# ASCII_04_LMS7002M_Misc.net
KiCad netlist of a schematic drawn in Altium Designer
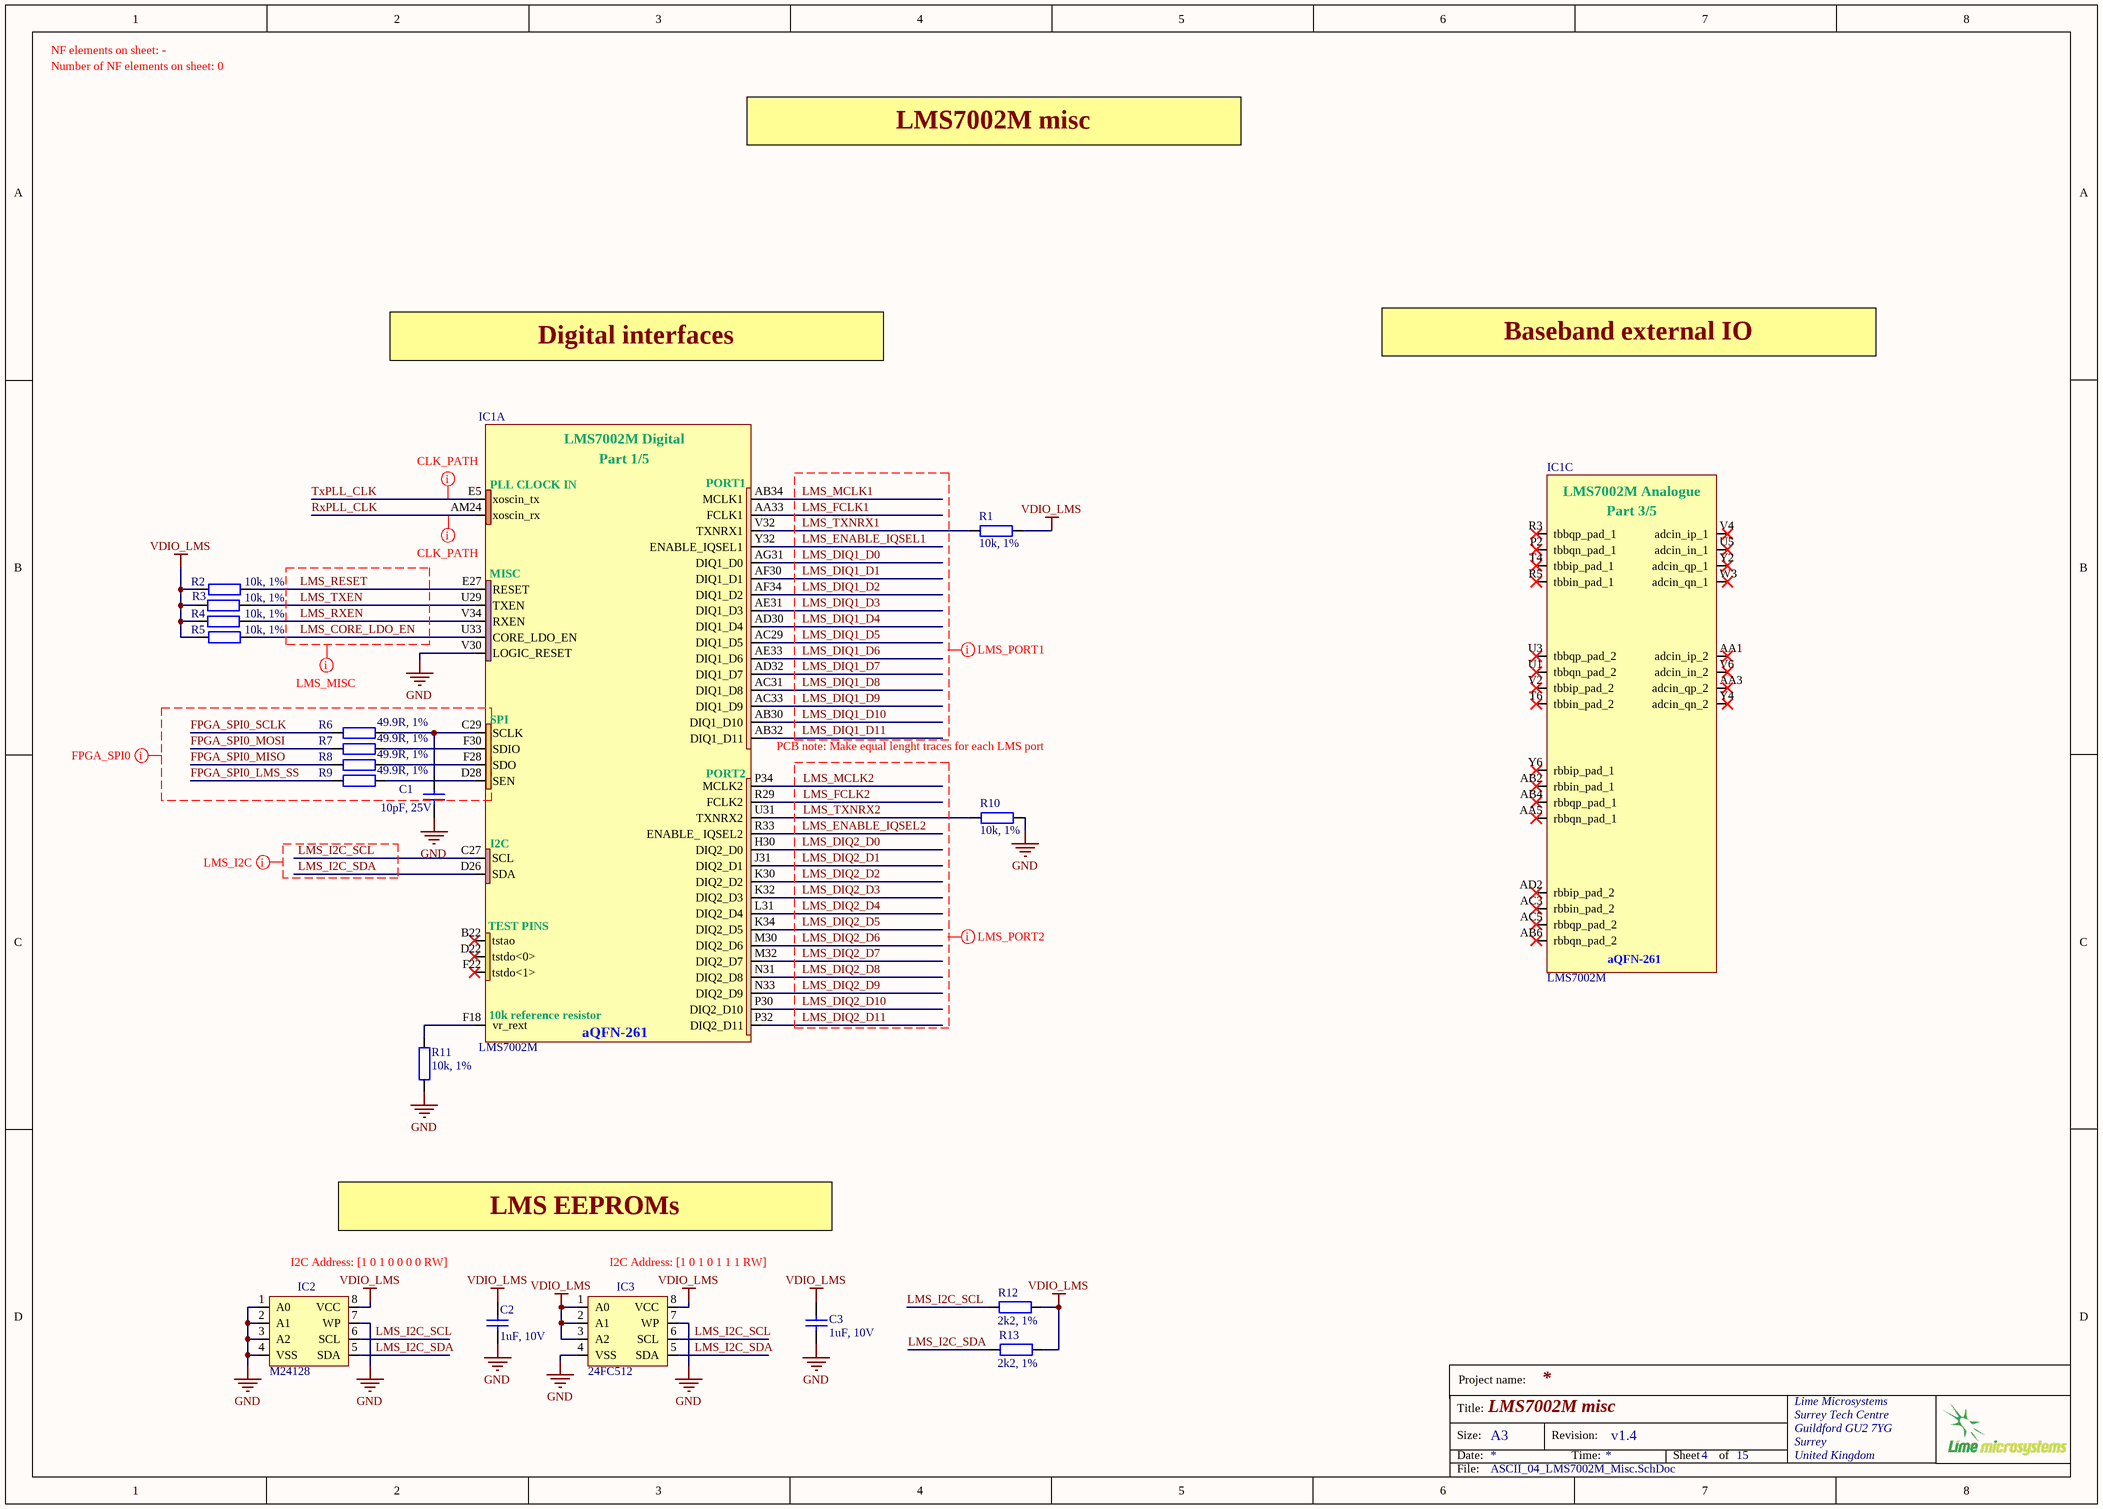
[diagram p0: ASCII_04_LMS7002M_Misc.SchDoc]

(export (version "E")
  (design (tool "Eeschema 10.0.6"))
  (components
    (comp (ref "C1")
      (value "10pF, 25V")
      (footprint "CAP0402")
      (fields (field (name "MANUFACTURER") "AVX"))
      (libsource (lib "LimeMicroAltiumLib_schLib") (part "Cap_0402"))
    )
    (comp (ref "C2")
      (value "1uF, 10V")
      (footprint "CAP0402")
      (fields (field (name "MANUFACTURER") "TDK"))
      (libsource (lib "LimeMicroAltiumLib_schLib") (part "Cap_0402"))
    )
    (comp (ref "C3")
      (value "1uF, 10V")
      (footprint "CAP0402")
      (fields (field (name "MANUFACTURER") "TDK"))
      (libsource (lib "LimeMicroAltiumLib_schLib") (part "Cap_0402"))
    )
    (comp (ref "IC1")
      (value "LMS7002M")
      (footprint "LMS7002M_v3")
      (fields (field (name "MANUFACTURER") "Lime Microsystems"))
      (libsource (lib "LimeMicroAltiumLib_schLib") (part "LMS7002M"))
    )
    (comp (ref "IC2")
      (value "M24128")
      (footprint "24FC512")
      (fields (field (name "MANUFACTURER") "STMicroelectronics"))
      (libsource (lib "LimeMicroAltiumLib_schLib") (part "24FC64F"))
    )
    (comp (ref "IC3")
      (value "24FC512")
      (footprint "24FC512")
      (fields (field (name "MANUFACTURER") "Microchip Technology"))
      (libsource (lib "LimeMicroAltiumLib_schLib") (part "24FC512"))
    )
    (comp (ref "R1")
      (value "10k, 1%")
      (footprint "RES0402")
      (fields (field (name "MANUFACTURER") "Yageo") (field (name "TOLERANCE") "±1%"))
      (libsource (lib "LimeMicroAltiumLib_schLib") (part "Res_0402"))
    )
    (comp (ref "R2")
      (value "10k, 1%")
      (footprint "RES0402")
      (fields (field (name "MANUFACTURER") "Yageo") (field (name "TOLERANCE") "±1%"))
      (libsource (lib "LimeMicroAltiumLib_schLib") (part "Res_0402"))
    )
    (comp (ref "R3")
      (value "10k, 1%")
      (footprint "RES0402")
      (fields (field (name "MANUFACTURER") "Yageo") (field (name "TOLERANCE") "±1%"))
      (libsource (lib "LimeMicroAltiumLib_schLib") (part "Res_0402"))
    )
    (comp (ref "R4")
      (value "10k, 1%")
      (footprint "RES0402")
      (fields (field (name "MANUFACTURER") "Yageo") (field (name "TOLERANCE") "±1%"))
      (libsource (lib "LimeMicroAltiumLib_schLib") (part "Res_0402"))
    )
    (comp (ref "R5")
      (value "10k, 1%")
      (footprint "RES0402")
      (fields (field (name "MANUFACTURER") "Yageo") (field (name "TOLERANCE") "±1%"))
      (libsource (lib "LimeMicroAltiumLib_schLib") (part "Res_0402"))
    )
    (comp (ref "R6")
      (value "49.9R, 1%")
      (footprint "RES0402")
      (fields
        (field (name "TOLERANCE") "±1%")
        (field (name "MANUFACTURER") "Samsung Electro-Mechanics America, Inc.")
        (field (name "MANUFACTURER PART NUMBER") "RC1005F49R9CS")
      )
      (libsource (lib "LimeMicroAltiumLib_schLib") (part "Res_0402"))
    )
    (comp (ref "R7")
      (value "49.9R, 1%")
      (footprint "RES0402")
      (fields
        (field (name "TOLERANCE") "±1%")
        (field (name "MANUFACTURER") "Samsung Electro-Mechanics America, Inc.")
        (field (name "MANUFACTURER PART NUMBER") "RC1005F49R9CS")
      )
      (libsource (lib "LimeMicroAltiumLib_schLib") (part "Res_0402"))
    )
    (comp (ref "R8")
      (value "49.9R, 1%")
      (footprint "RES0402")
      (fields
        (field (name "TOLERANCE") "±1%")
        (field (name "MANUFACTURER") "Samsung Electro-Mechanics America, Inc.")
        (field (name "MANUFACTURER PART NUMBER") "RC1005F49R9CS")
      )
      (libsource (lib "LimeMicroAltiumLib_schLib") (part "Res_0402"))
    )
    (comp (ref "R9")
      (value "49.9R, 1%")
      (footprint "RES0402")
      (fields
        (field (name "TOLERANCE") "±1%")
        (field (name "MANUFACTURER") "Samsung Electro-Mechanics America, Inc.")
        (field (name "MANUFACTURER PART NUMBER") "RC1005F49R9CS")
      )
      (libsource (lib "LimeMicroAltiumLib_schLib") (part "Res_0402"))
    )
    (comp (ref "R10")
      (value "10k, 1%")
      (footprint "RES0402")
      (fields (field (name "MANUFACTURER") "Yageo") (field (name "TOLERANCE") "±1%"))
      (libsource (lib "LimeMicroAltiumLib_schLib") (part "Res_0402"))
    )
    (comp (ref "R11")
      (value "10k, 1%")
      (footprint "RES0402")
      (fields (field (name "MANUFACTURER") "Yageo") (field (name "TOLERANCE") "±1%"))
      (libsource (lib "LimeMicroAltiumLib_schLib") (part "Res_0402"))
    )
    (comp (ref "R12")
      (value "2k2, 1%")
      (footprint "RES0402")
      (fields (field (name "MANUFACTURER") "Stackpole Electronics Inc") (field (name "TOLERANCE") "±1%"))
      (libsource (lib "LimeMicroAltiumLib_schLib") (part "Res_0402"))
    )
    (comp (ref "R13")
      (value "2k2, 1%")
      (footprint "RES0402")
      (fields (field (name "MANUFACTURER") "Stackpole Electronics Inc") (field (name "TOLERANCE") "±1%"))
      (libsource (lib "LimeMicroAltiumLib_schLib") (part "Res_0402"))
    )
  )
  (nets
    (net (code "1") (name "/FPGA_SPI0_LMS_SS") (class "Default")
      (node (ref "R9") (pin "2") (pinfunction "2_2") (pintype "passive"))
    )
    (net (code "2") (name "/FPGA_SPI0_MISO") (class "Default")
      (node (ref "R8") (pin "2") (pinfunction "2_2") (pintype "passive"))
    )
    (net (code "3") (name "/FPGA_SPI0_MOSI") (class "Default")
      (node (ref "R7") (pin "2") (pinfunction "2_2") (pintype "passive"))
    )
    (net (code "4") (name "/FPGA_SPI0_SCLK") (class "Default")
      (node (ref "R6") (pin "2") (pinfunction "2_2") (pintype "passive"))
    )
    (net (code "5") (name "/LMS_CORE_LDO_EN") (class "Default")
      (node (ref "IC1") (pin "U33") (pinfunction "CORE_LDO_EN_U33") (pintype "passive"))
      (node (ref "R5") (pin "1") (pinfunction "1_1") (pintype "passive"))
    )
    (net (code "6") (name "/LMS_DIQ1_D0") (class "Default")
      (node (ref "IC1") (pin "AG31") (pinfunction "DIQ1_D0_AG31") (pintype "passive"))
    )
    (net (code "7") (name "/LMS_DIQ1_D1") (class "Default")
      (node (ref "IC1") (pin "AF30") (pinfunction "DIQ1_D1_AF30") (pintype "passive"))
    )
    (net (code "8") (name "/LMS_DIQ1_D2") (class "Default")
      (node (ref "IC1") (pin "AF34") (pinfunction "DIQ1_D2_AF34") (pintype "passive"))
    )
    (net (code "9") (name "/LMS_DIQ1_D3") (class "Default")
      (node (ref "IC1") (pin "AE31") (pinfunction "DIQ1_D3_AE31") (pintype "passive"))
    )
    (net (code "10") (name "/LMS_DIQ1_D4") (class "Default")
      (node (ref "IC1") (pin "AD30") (pinfunction "DIQ1_D4_AD30") (pintype "passive"))
    )
    (net (code "11") (name "/LMS_DIQ1_D5") (class "Default")
      (node (ref "IC1") (pin "AC29") (pinfunction "DIQ1_D5_AC29") (pintype "passive"))
    )
    (net (code "12") (name "/LMS_DIQ1_D6") (class "Default")
      (node (ref "IC1") (pin "AE33") (pinfunction "DIQ1_D6_AE33") (pintype "passive"))
    )
    (net (code "13") (name "/LMS_DIQ1_D7") (class "Default")
      (node (ref "IC1") (pin "AD32") (pinfunction "DIQ1_D7_AD32") (pintype "passive"))
    )
    (net (code "14") (name "/LMS_DIQ1_D8") (class "Default")
      (node (ref "IC1") (pin "AC31") (pinfunction "DIQ1_D8_AC31") (pintype "passive"))
    )
    (net (code "15") (name "/LMS_DIQ1_D9") (class "Default")
      (node (ref "IC1") (pin "AC33") (pinfunction "DIQ1_D9_AC33") (pintype "passive"))
    )
    (net (code "16") (name "/LMS_DIQ1_D10") (class "Default")
      (node (ref "IC1") (pin "AB30") (pinfunction "DIQ1_D10_AB30") (pintype "passive"))
    )
    (net (code "17") (name "/LMS_DIQ1_D11") (class "Default")
      (node (ref "IC1") (pin "AB32") (pinfunction "DIQ1_D11_AB32") (pintype "passive"))
    )
    (net (code "18") (name "/LMS_DIQ2_D0") (class "Default")
      (node (ref "IC1") (pin "H30") (pinfunction "DIQ2_D0_H30") (pintype "passive"))
    )
    (net (code "19") (name "/LMS_DIQ2_D1") (class "Default")
      (node (ref "IC1") (pin "J31") (pinfunction "DIQ2_D1_J31") (pintype "passive"))
    )
    (net (code "20") (name "/LMS_DIQ2_D2") (class "Default")
      (node (ref "IC1") (pin "K30") (pinfunction "DIQ2_D2_K30") (pintype "passive"))
    )
    (net (code "21") (name "/LMS_DIQ2_D3") (class "Default")
      (node (ref "IC1") (pin "K32") (pinfunction "DIQ2_D3_K32") (pintype "passive"))
    )
    (net (code "22") (name "/LMS_DIQ2_D4") (class "Default")
      (node (ref "IC1") (pin "L31") (pinfunction "DIQ2_D4_L31") (pintype "passive"))
    )
    (net (code "23") (name "/LMS_DIQ2_D5") (class "Default")
      (node (ref "IC1") (pin "K34") (pinfunction "DIQ2_D5_K34") (pintype "passive"))
    )
    (net (code "24") (name "/LMS_DIQ2_D6") (class "Default")
      (node (ref "IC1") (pin "M30") (pinfunction "DIQ2_D6_M30") (pintype "passive"))
    )
    (net (code "25") (name "/LMS_DIQ2_D7") (class "Default")
      (node (ref "IC1") (pin "M32") (pinfunction "DIQ2_D7_M32") (pintype "passive"))
    )
    (net (code "26") (name "/LMS_DIQ2_D8") (class "Default")
      (node (ref "IC1") (pin "N31") (pinfunction "DIQ2_D8_N31") (pintype "passive"))
    )
    (net (code "27") (name "/LMS_DIQ2_D9") (class "Default")
      (node (ref "IC1") (pin "N33") (pinfunction "DIQ2_D9_N33") (pintype "passive"))
    )
    (net (code "28") (name "/LMS_DIQ2_D10") (class "Default")
      (node (ref "IC1") (pin "P30") (pinfunction "DIQ2_D10_P30") (pintype "passive"))
    )
    (net (code "29") (name "/LMS_DIQ2_D11") (class "Default")
      (node (ref "IC1") (pin "P32") (pinfunction "DIQ2_D11_P32") (pintype "passive"))
    )
    (net (code "30") (name "/LMS_ENABLE_IQSEL1") (class "Default")
      (node (ref "IC1") (pin "Y32") (pinfunction "ENABLE_IQSEL1_Y32") (pintype "passive"))
    )
    (net (code "31") (name "/LMS_ENABLE_IQSEL2") (class "Default")
      (node (ref "IC1") (pin "R33") (pinfunction "ENABLE__IQSEL2_R33") (pintype "passive"))
    )
    (net (code "32") (name "/LMS_FCLK1") (class "Default")
      (node (ref "IC1") (pin "AA33") (pinfunction "FCLK1_AA33") (pintype "passive"))
    )
    (net (code "33") (name "/LMS_FCLK2") (class "Default")
      (node (ref "IC1") (pin "R29") (pinfunction "FCLK2_R29") (pintype "passive"))
    )
    (net (code "34") (name "/LMS_I2C_SCL") (class "Default")
      (node (ref "IC1") (pin "C27") (pinfunction "SCL_C27") (pintype "passive"))
      (node (ref "IC2") (pin "6") (pinfunction "SCL_6") (pintype "passive"))
      (node (ref "IC3") (pin "6") (pinfunction "SCL_6") (pintype "passive"))
      (node (ref "R12") (pin "2") (pinfunction "2_2") (pintype "passive"))
    )
    (net (code "35") (name "/LMS_I2C_SDA") (class "Default")
      (node (ref "IC1") (pin "D26") (pinfunction "SDA_D26") (pintype "passive"))
      (node (ref "IC2") (pin "5") (pinfunction "SDA_5") (pintype "passive"))
      (node (ref "IC3") (pin "5") (pinfunction "SDA_5") (pintype "passive"))
      (node (ref "R13") (pin "2") (pinfunction "2_2") (pintype "passive"))
    )
    (net (code "36") (name "/LMS_MCLK1") (class "Default")
      (node (ref "IC1") (pin "AB34") (pinfunction "MCLK1_AB34") (pintype "passive"))
    )
    (net (code "37") (name "/LMS_MCLK2") (class "Default")
      (node (ref "IC1") (pin "P34") (pinfunction "MCLK2_P34") (pintype "passive"))
    )
    (net (code "38") (name "/LMS_RESET") (class "Default")
      (node (ref "IC1") (pin "E27") (pinfunction "RESET_E27") (pintype "passive"))
      (node (ref "R2") (pin "1") (pinfunction "1_1") (pintype "passive"))
    )
    (net (code "39") (name "/LMS_RXEN") (class "Default")
      (node (ref "IC1") (pin "V34") (pinfunction "RXEN_V34") (pintype "passive"))
      (node (ref "R4") (pin "2") (pinfunction "2_2") (pintype "passive"))
    )
    (net (code "40") (name "/LMS_TXEN") (class "Default")
      (node (ref "IC1") (pin "U29") (pinfunction "TXEN_U29") (pintype "passive"))
      (node (ref "R3") (pin "2") (pinfunction "2_2") (pintype "passive"))
    )
    (net (code "41") (name "/LMS_TXNRX1") (class "Default")
      (node (ref "IC1") (pin "V32") (pinfunction "TXNRX1_V32") (pintype "passive"))
      (node (ref "R1") (pin "1") (pinfunction "1_1") (pintype "passive"))
    )
    (net (code "42") (name "/LMS_TXNRX2") (class "Default")
      (node (ref "IC1") (pin "U31") (pinfunction "TXNRX2_U31") (pintype "passive"))
      (node (ref "R10") (pin "2") (pinfunction "2_2") (pintype "passive"))
    )
    (net (code "43") (name "/RxPLL_CLK") (class "Default")
      (node (ref "IC1") (pin "AM24") (pinfunction "xoscin_rx_AM24") (pintype "passive"))
    )
    (net (code "44") (name "/TxPLL_CLK") (class "Default")
      (node (ref "IC1") (pin "E5") (pinfunction "xoscin_tx_E5") (pintype "passive"))
    )
    (net (code "45") (name "GND") (class "Default")
      (node (ref "C1") (pin "2") (pinfunction "2_2") (pintype "passive"))
      (node (ref "C2") (pin "2") (pinfunction "2_2") (pintype "passive"))
      (node (ref "C3") (pin "1") (pinfunction "1_1") (pintype "passive"))
      (node (ref "IC1") (pin "V30") (pinfunction "LOGIC_RESET_V30") (pintype "passive"))
      (node (ref "IC2") (pin "1") (pinfunction "A0_1") (pintype "passive"))
      (node (ref "IC2") (pin "2") (pinfunction "A1_2") (pintype "passive"))
      (node (ref "IC2") (pin "3") (pinfunction "A2_3") (pintype "passive"))
      (node (ref "IC2") (pin "4") (pinfunction "VSS_4") (pintype "passive"))
      (node (ref "IC2") (pin "7") (pinfunction "WP_7") (pintype "passive"))
      (node (ref "IC3") (pin "4") (pinfunction "VSS_4") (pintype "passive"))
      (node (ref "IC3") (pin "7") (pinfunction "WP_7") (pintype "passive"))
      (node (ref "R10") (pin "1") (pinfunction "1_1") (pintype "passive"))
      (node (ref "R11") (pin "2") (pinfunction "2_2") (pintype "passive"))
    )
    (net (code "46") (name "Net-(IC1A-SCLK)") (class "Default")
      (node (ref "C1") (pin "1") (pinfunction "1_1") (pintype "passive"))
      (node (ref "IC1") (pin "C29") (pinfunction "SCLK_C29") (pintype "passive"))
      (node (ref "R6") (pin "1") (pinfunction "1_1") (pintype "passive"))
    )
    (net (code "47") (name "Net-(IC1A-SDIO)") (class "Default")
      (node (ref "IC1") (pin "F30") (pinfunction "SDIO_F30") (pintype "passive"))
      (node (ref "R7") (pin "1") (pinfunction "1_1") (pintype "passive"))
    )
    (net (code "48") (name "Net-(IC1A-SDO)") (class "Default")
      (node (ref "IC1") (pin "F28") (pinfunction "SDO_F28") (pintype "passive"))
      (node (ref "R8") (pin "1") (pinfunction "1_1") (pintype "passive"))
    )
    (net (code "49") (name "Net-(IC1A-SEN)") (class "Default")
      (node (ref "IC1") (pin "D28") (pinfunction "SEN_D28") (pintype "passive"))
      (node (ref "R9") (pin "1") (pinfunction "1_1") (pintype "passive"))
    )
    (net (code "50") (name "Net-(IC1A-vr_rext)") (class "Default")
      (node (ref "IC1") (pin "F18") (pinfunction "vr_rext_F18") (pintype "passive"))
      (node (ref "R11") (pin "1") (pinfunction "1_1") (pintype "passive"))
    )
    (net (code "51") (name "VDIO_LMS") (class "Default")
      (node (ref "C2") (pin "1") (pinfunction "1_1") (pintype "passive"))
      (node (ref "C3") (pin "2") (pinfunction "2_2") (pintype "passive"))
      (node (ref "IC2") (pin "8") (pinfunction "VCC_8") (pintype "passive"))
      (node (ref "IC3") (pin "1") (pinfunction "A0_1") (pintype "passive"))
      (node (ref "IC3") (pin "2") (pinfunction "A1_2") (pintype "passive"))
      (node (ref "IC3") (pin "3") (pinfunction "A2_3") (pintype "passive"))
      (node (ref "IC3") (pin "8") (pinfunction "VCC_8") (pintype "passive"))
      (node (ref "R1") (pin "2") (pinfunction "2_2") (pintype "passive"))
      (node (ref "R12") (pin "1") (pinfunction "1_1") (pintype "passive"))
      (node (ref "R13") (pin "1") (pinfunction "1_1") (pintype "passive"))
      (node (ref "R2") (pin "2") (pinfunction "2_2") (pintype "passive"))
      (node (ref "R3") (pin "1") (pinfunction "1_1") (pintype "passive"))
      (node (ref "R4") (pin "1") (pinfunction "1_1") (pintype "passive"))
      (node (ref "R5") (pin "2") (pinfunction "2_2") (pintype "passive"))
    )
    (net (code "52") (name "unconnected-(IC1A-tstao-PadB22)") (class "Default")
      (node (ref "IC1") (pin "B22") (pinfunction "tstao_B22") (pintype "passive+no_connect"))
    )
    (net (code "53") (name "unconnected-(IC1A-tstdo<0>-PadD22)") (class "Default")
      (node (ref "IC1") (pin "D22") (pinfunction "tstdo<0>_D22") (pintype "passive+no_connect"))
    )
    (net (code "54") (name "unconnected-(IC1A-tstdo<1>-PadF22)") (class "Default")
      (node (ref "IC1") (pin "F22") (pinfunction "tstdo<1>_F22") (pintype "passive+no_connect"))
    )
    (net (code "55") (name "unconnected-(IC1C-adcin_in_1-PadU5)") (class "Default")
      (node (ref "IC1") (pin "U5") (pinfunction "adcin_in_1_U5") (pintype "passive+no_connect"))
    )
    (net (code "56") (name "unconnected-(IC1C-adcin_in_2-PadV6)") (class "Default")
      (node (ref "IC1") (pin "V6") (pinfunction "adcin_in_2_V6") (pintype "passive+no_connect"))
    )
    (net (code "57") (name "unconnected-(IC1C-adcin_ip_1-PadV4)") (class "Default")
      (node (ref "IC1") (pin "V4") (pinfunction "adcin_ip_1_V4") (pintype "passive+no_connect"))
    )
    (net (code "58") (name "unconnected-(IC1C-adcin_ip_2-PadAA1)") (class "Default")
      (node (ref "IC1") (pin "AA1") (pinfunction "adcin_ip_2_AA1") (pintype "passive+no_connect"))
    )
    (net (code "59") (name "unconnected-(IC1C-adcin_qn_1-PadW3)") (class "Default")
      (node (ref "IC1") (pin "W3") (pinfunction "adcin_qn_1_W3") (pintype "passive+no_connect"))
    )
    (net (code "60") (name "unconnected-(IC1C-adcin_qn_2-PadY4)") (class "Default")
      (node (ref "IC1") (pin "Y4") (pinfunction "adcin_qn_2_Y4") (pintype "passive+no_connect"))
    )
    (net (code "61") (name "unconnected-(IC1C-adcin_qp_1-PadY2)") (class "Default")
      (node (ref "IC1") (pin "Y2") (pinfunction "adcin_qp_1_Y2") (pintype "passive+no_connect"))
    )
    (net (code "62") (name "unconnected-(IC1C-adcin_qp_2-PadAA3)") (class "Default")
      (node (ref "IC1") (pin "AA3") (pinfunction "adcin_qp_2_AA3") (pintype "passive+no_connect"))
    )
    (net (code "63") (name "unconnected-(IC1C-rbbin_pad_1-PadAB2)") (class "Default")
      (node (ref "IC1") (pin "AB2") (pinfunction "rbbin_pad_1_AB2") (pintype "passive+no_connect"))
    )
    (net (code "64") (name "unconnected-(IC1C-rbbin_pad_2-PadAC3)") (class "Default")
      (node (ref "IC1") (pin "AC3") (pinfunction "rbbin_pad_2_AC3") (pintype "passive+no_connect"))
    )
    (net (code "65") (name "unconnected-(IC1C-rbbip_pad_1-PadY6)") (class "Default")
      (node (ref "IC1") (pin "Y6") (pinfunction "rbbip_pad_1_Y6") (pintype "passive+no_connect"))
    )
    (net (code "66") (name "unconnected-(IC1C-rbbip_pad_2-PadAD2)") (class "Default")
      (node (ref "IC1") (pin "AD2") (pinfunction "rbbip_pad_2_AD2") (pintype "passive+no_connect"))
    )
    (net (code "67") (name "unconnected-(IC1C-rbbqn_pad_1-PadAA5)") (class "Default")
      (node (ref "IC1") (pin "AA5") (pinfunction "rbbqn_pad_1_AA5") (pintype "passive+no_connect"))
    )
    (net (code "68") (name "unconnected-(IC1C-rbbqn_pad_2-PadAB6)") (class "Default")
      (node (ref "IC1") (pin "AB6") (pinfunction "rbbqn_pad_2_AB6") (pintype "passive+no_connect"))
    )
    (net (code "69") (name "unconnected-(IC1C-rbbqp_pad_1-PadAB4)") (class "Default")
      (node (ref "IC1") (pin "AB4") (pinfunction "rbbqp_pad_1_AB4") (pintype "passive+no_connect"))
    )
    (net (code "70") (name "unconnected-(IC1C-rbbqp_pad_2-PadAC5)") (class "Default")
      (node (ref "IC1") (pin "AC5") (pinfunction "rbbqp_pad_2_AC5") (pintype "passive+no_connect"))
    )
    (net (code "71") (name "unconnected-(IC1C-tbbin_pad_1-PadR5)") (class "Default")
      (node (ref "IC1") (pin "R5") (pinfunction "tbbin_pad_1_R5") (pintype "passive+no_connect"))
    )
    (net (code "72") (name "unconnected-(IC1C-tbbin_pad_2-PadT6)") (class "Default")
      (node (ref "IC1") (pin "T6") (pinfunction "tbbin_pad_2_T6") (pintype "passive+no_connect"))
    )
    (net (code "73") (name "unconnected-(IC1C-tbbip_pad_1-PadT4)") (class "Default")
      (node (ref "IC1") (pin "T4") (pinfunction "tbbip_pad_1_T4") (pintype "passive+no_connect"))
    )
    (net (code "74") (name "unconnected-(IC1C-tbbip_pad_2-PadV2)") (class "Default")
      (node (ref "IC1") (pin "V2") (pinfunction "tbbip_pad_2_V2") (pintype "passive+no_connect"))
    )
    (net (code "75") (name "unconnected-(IC1C-tbbqn_pad_1-PadP2)") (class "Default")
      (node (ref "IC1") (pin "P2") (pinfunction "tbbqn_pad_1_P2") (pintype "passive+no_connect"))
    )
    (net (code "76") (name "unconnected-(IC1C-tbbqn_pad_2-PadU1)") (class "Default")
      (node (ref "IC1") (pin "U1") (pinfunction "tbbqn_pad_2_U1") (pintype "passive+no_connect"))
    )
    (net (code "77") (name "unconnected-(IC1C-tbbqp_pad_1-PadR3)") (class "Default")
      (node (ref "IC1") (pin "R3") (pinfunction "tbbqp_pad_1_R3") (pintype "passive+no_connect"))
    )
    (net (code "78") (name "unconnected-(IC1C-tbbqp_pad_2-PadU3)") (class "Default")
      (node (ref "IC1") (pin "U3") (pinfunction "tbbqp_pad_2_U3") (pintype "passive+no_connect"))
    )
  )
)
